# stepper_motor.net
KiCad netlist of a schematic drawn in Altium Designer
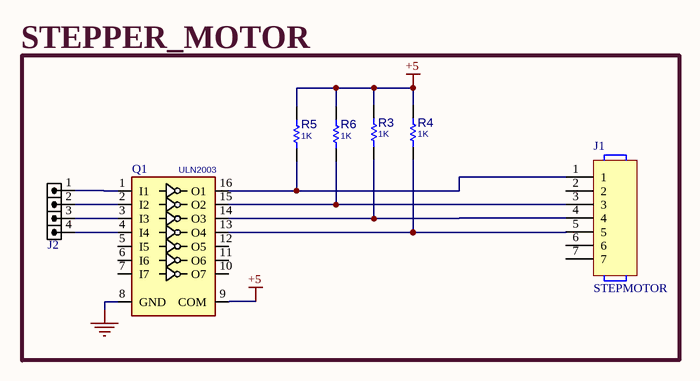
[diagram p0: stepper_motor.SchDoc]

(export (version "E")
  (design (tool "Eeschema 10.0.6"))
  (components
    (comp (ref "J1")
      (value "STEPMOTOR")
      (libsource (lib "AvrDevelopmentBoard") (part "STEP_MOTOR_CONNECTOR"))
    )
    (comp (ref "J2")
      (value "HDR1X4")
      (footprint "HDRMINI_M_1X4")
      (description "CONN, HEADER, Male, pitch: 1.27mm, 4POS")
      (libsource (lib "conn_header_1.27mm_st") (part "HDRMINI_M_1X4"))
    )
    (comp (ref "Q1")
      (value "ULN2003")
      (footprint "DIP_16")
      (description "Darlington, 7-CH, 50V, 0.5A")
      (fields (field (name "MANF_P#") "ULN2003A") (field (name "MANF") "DIODES"))
      (libsource (lib "transistor_bjt") (part "ULN2003_DIP16"))
    )
    (comp (ref "R3")
      (value "1K")
      (footprint "R025W_AX04")
      (description "RESISTOR, THD")
      (fields (field (name "MANF_P#") "RK73H1ETTP4701F") (field (name "MANF") "KOA SPEER"))
      (libsource (lib "passive_thd") (part "RES_THD"))
    )
    (comp (ref "R4")
      (value "1K")
      (footprint "R025W_AX04")
      (description "RESISTOR, THD")
      (fields (field (name "MANF_P#") "RK73H1ETTP4701F") (field (name "MANF") "KOA SPEER"))
      (libsource (lib "passive_thd") (part "RES_THD"))
    )
    (comp (ref "R5")
      (value "1K")
      (footprint "R025W_AX04")
      (description "RESISTOR, THD")
      (fields (field (name "MANF_P#") "RK73H1ETTP4701F") (field (name "MANF") "KOA SPEER"))
      (libsource (lib "passive_thd") (part "RES_THD"))
    )
    (comp (ref "R6")
      (value "1K")
      (footprint "R025W_AX04")
      (description "RESISTOR, THD")
      (fields (field (name "MANF_P#") "RK73H1ETTP4701F") (field (name "MANF") "KOA SPEER"))
      (libsource (lib "passive_thd") (part "RES_THD"))
    )
  )
  (nets
    (net (code "1") (name "+5") (class "Default")
      (node (ref "Q1") (pin "9") (pinfunction "COM_9") (pintype "passive"))
      (node (ref "R3") (pin "1") (pinfunction "1_1") (pintype "passive"))
      (node (ref "R4") (pin "1") (pinfunction "1_1") (pintype "passive"))
      (node (ref "R5") (pin "1") (pinfunction "1_1") (pintype "passive"))
      (node (ref "R6") (pin "1") (pinfunction "1_1") (pintype "passive"))
    )
    (net (code "2") (name "GND") (class "Default")
      (node (ref "Q1") (pin "8") (pinfunction "GND_8") (pintype "passive"))
    )
    (net (code "3") (name "Net-(Q1-I1)") (class "Default")
      (node (ref "J2") (pin "1") (pinfunction "1_1") (pintype "passive"))
      (node (ref "Q1") (pin "1") (pinfunction "I1_1") (pintype "passive"))
    )
    (net (code "4") (name "Net-(Q1-I2)") (class "Default")
      (node (ref "J2") (pin "2") (pinfunction "2_2") (pintype "passive"))
      (node (ref "Q1") (pin "2") (pinfunction "I2_2") (pintype "passive"))
    )
    (net (code "5") (name "Net-(Q1-I3)") (class "Default")
      (node (ref "J2") (pin "3") (pinfunction "3_3") (pintype "passive"))
      (node (ref "Q1") (pin "3") (pinfunction "I3_3") (pintype "passive"))
    )
    (net (code "6") (name "Net-(Q1-I4)") (class "Default")
      (node (ref "J2") (pin "4") (pinfunction "4_4") (pintype "passive"))
      (node (ref "Q1") (pin "4") (pinfunction "I4_4") (pintype "passive"))
    )
    (net (code "7") (name "Net-(Q1-O1)") (class "Default")
      (node (ref "J1") (pin "1") (pinfunction "1_1") (pintype "passive"))
      (node (ref "Q1") (pin "16") (pinfunction "O1_16") (pintype "passive"))
      (node (ref "R5") (pin "2") (pinfunction "2_2") (pintype "passive"))
    )
    (net (code "8") (name "Net-(Q1-O2)") (class "Default")
      (node (ref "J1") (pin "3") (pinfunction "3_3") (pintype "passive"))
      (node (ref "Q1") (pin "15") (pinfunction "O2_15") (pintype "passive"))
      (node (ref "R6") (pin "2") (pinfunction "2_2") (pintype "passive"))
    )
    (net (code "9") (name "Net-(Q1-O3)") (class "Default")
      (node (ref "J1") (pin "4") (pinfunction "4_4") (pintype "passive"))
      (node (ref "Q1") (pin "14") (pinfunction "O3_14") (pintype "passive"))
      (node (ref "R3") (pin "2") (pinfunction "2_2") (pintype "passive"))
    )
    (net (code "10") (name "Net-(Q1-O4)") (class "Default")
      (node (ref "J1") (pin "5") (pinfunction "5_5") (pintype "passive"))
      (node (ref "Q1") (pin "13") (pinfunction "O4_13") (pintype "passive"))
      (node (ref "R4") (pin "2") (pinfunction "2_2") (pintype "passive"))
    )
    (net (code "11") (name "unconnected-(J1-Pad2)") (class "Default")
      (node (ref "J1") (pin "2") (pinfunction "2_2") (pintype "passive"))
    )
    (net (code "12") (name "unconnected-(J1-Pad6)") (class "Default")
      (node (ref "J1") (pin "6") (pinfunction "6_6") (pintype "passive"))
    )
    (net (code "13") (name "unconnected-(J1-Pad7)") (class "Default")
      (node (ref "J1") (pin "7") (pinfunction "7_7") (pintype "passive"))
    )
    (net (code "14") (name "unconnected-(Q1-I5-Pad5)") (class "Default")
      (node (ref "Q1") (pin "5") (pinfunction "I5_5") (pintype "passive"))
    )
    (net (code "15") (name "unconnected-(Q1-I6-Pad6)") (class "Default")
      (node (ref "Q1") (pin "6") (pinfunction "I6_6") (pintype "passive"))
    )
    (net (code "16") (name "unconnected-(Q1-I7-Pad7)") (class "Default")
      (node (ref "Q1") (pin "7") (pinfunction "I7_7") (pintype "passive"))
    )
    (net (code "17") (name "unconnected-(Q1-O5-Pad12)") (class "Default")
      (node (ref "Q1") (pin "12") (pinfunction "O5_12") (pintype "passive"))
    )
    (net (code "18") (name "unconnected-(Q1-O6-Pad11)") (class "Default")
      (node (ref "Q1") (pin "11") (pinfunction "O6_11") (pintype "passive"))
    )
    (net (code "19") (name "unconnected-(Q1-O7-Pad10)") (class "Default")
      (node (ref "Q1") (pin "10") (pinfunction "O7_10") (pintype "passive"))
    )
  )
)
